# Clock.net
KiCad netlist of a schematic drawn in Altium Designer
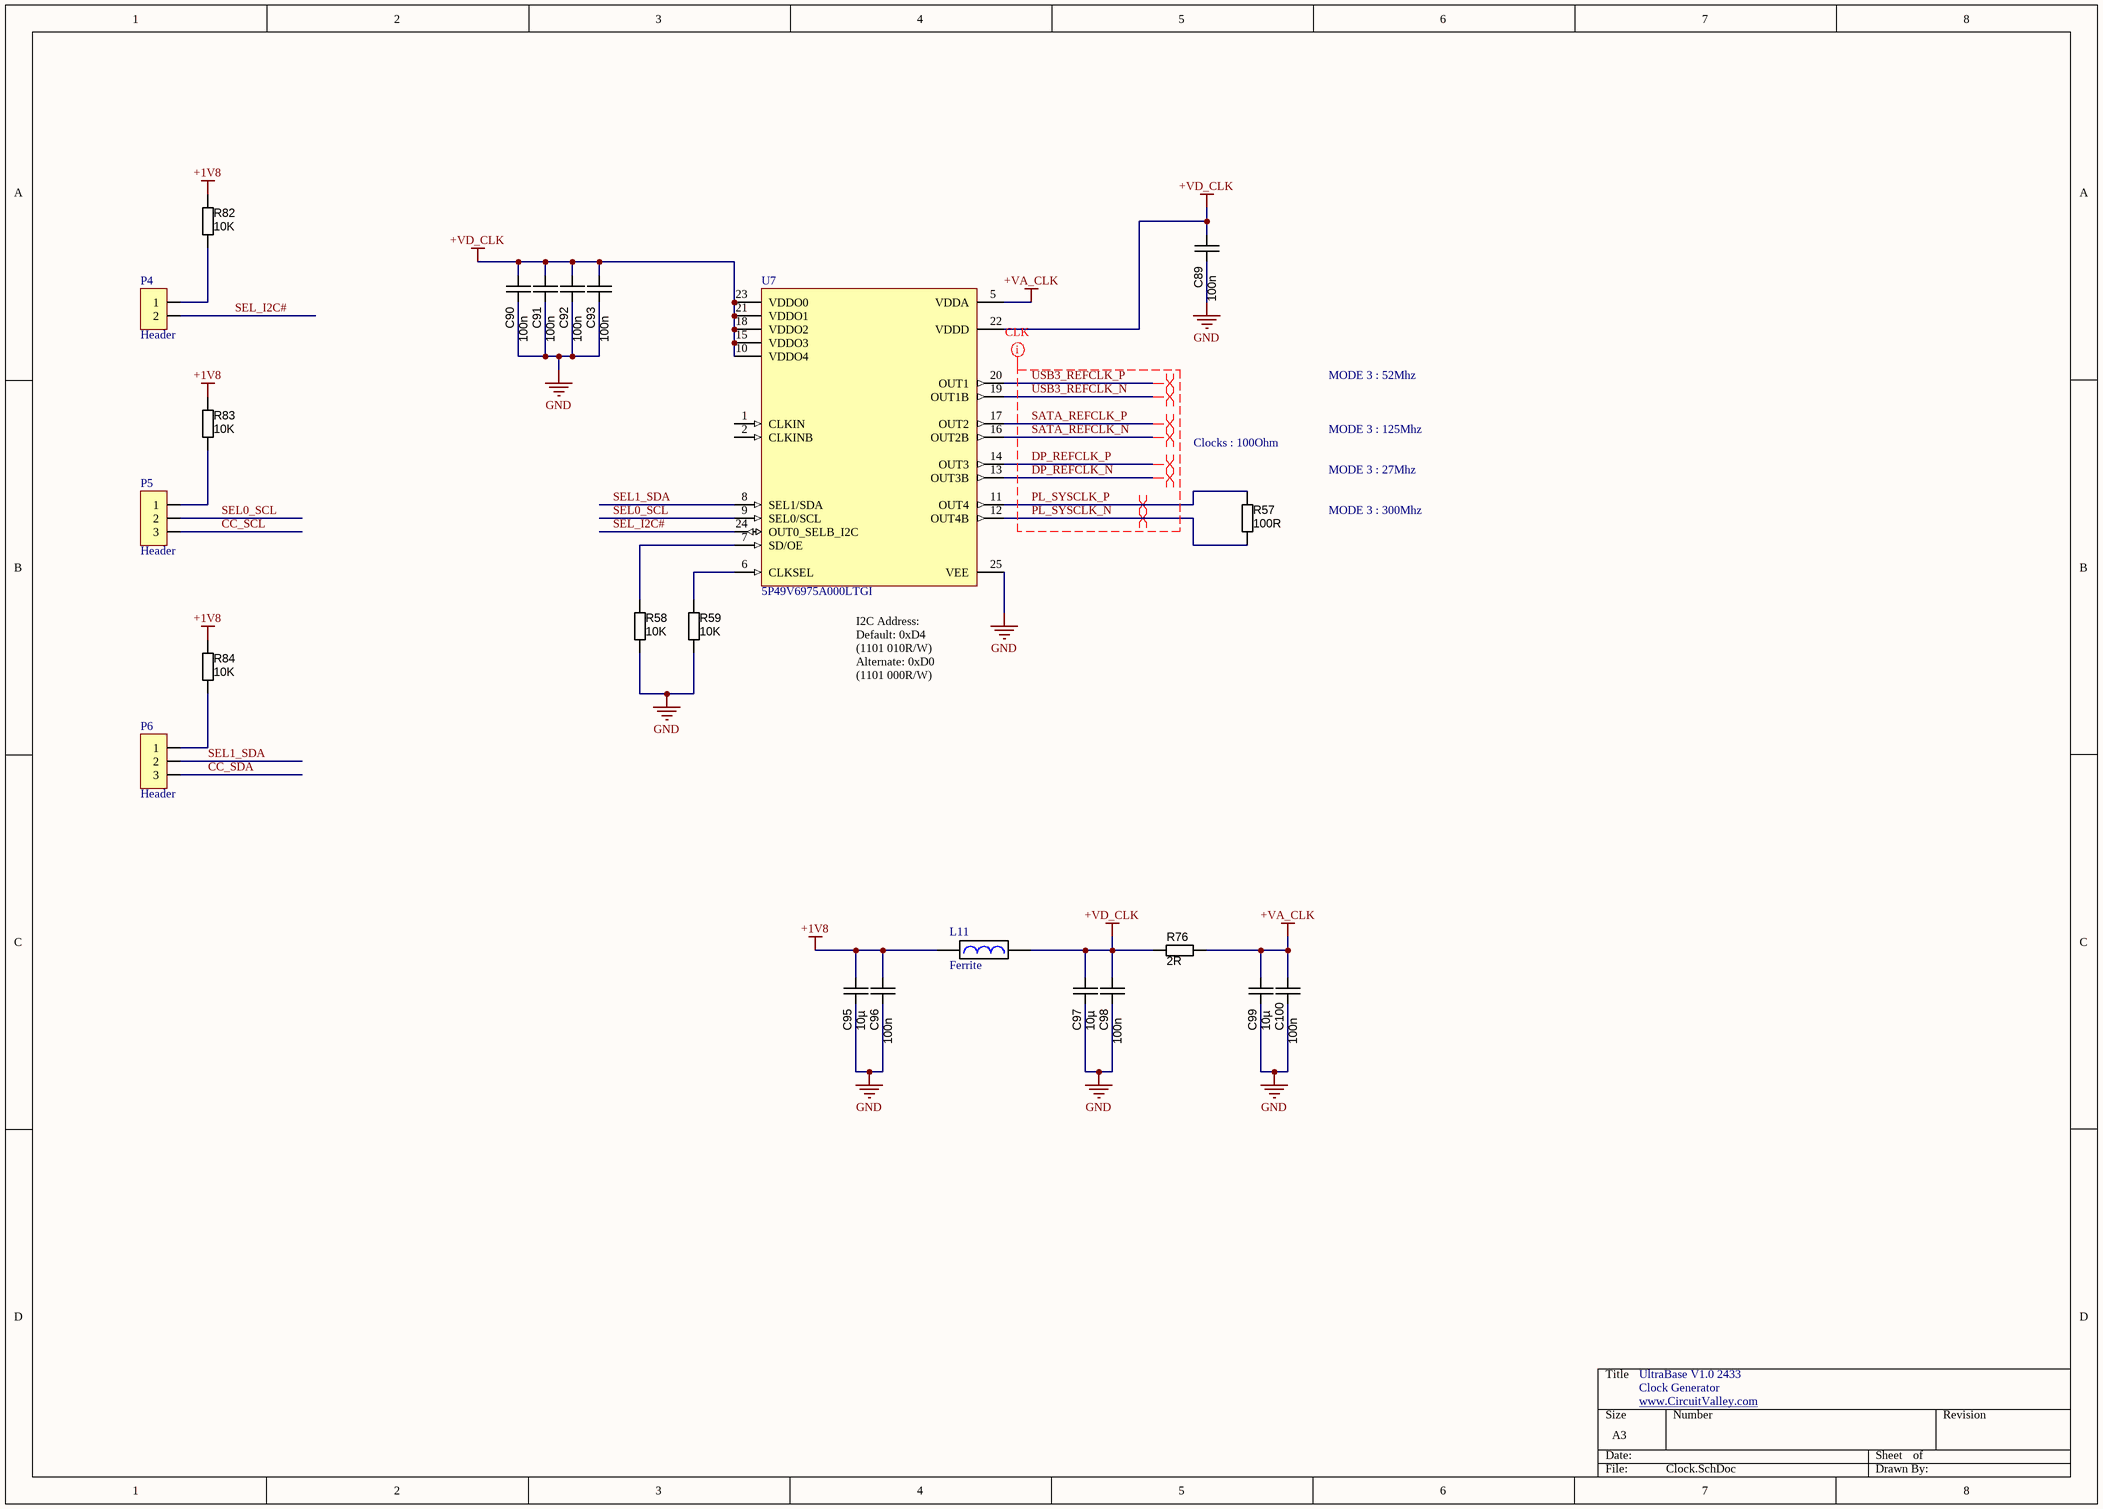
[diagram p0: Clock.SchDoc]

(export (version "E")
  (design (tool "Eeschema 10.0.6"))
  (components
    (comp (ref "C89")
      (value "100n")
      (footprint "CAPC1608N")
      (description "Capacitor SMD Cer 120pF 10% 50V C0G 0603")
      (fields (field (name "TOLERANCE") "±10%"))
      (libsource (lib "PBL - Capacitors") (part "CAPC_120p_0603_C0G_50V"))
    )
    (comp (ref "C90")
      (value "100n")
      (footprint "CAPC1608N")
      (description "Capacitor SMD Cer 120pF 10% 50V C0G 0603")
      (fields (field (name "TOLERANCE") "±10%"))
      (libsource (lib "PBL - Capacitors") (part "CAPC_120p_0603_C0G_50V"))
    )
    (comp (ref "C91")
      (value "100n")
      (footprint "CAPC1608N")
      (description "Capacitor SMD Cer 120pF 10% 50V C0G 0603")
      (fields (field (name "TOLERANCE") "±10%"))
      (libsource (lib "PBL - Capacitors") (part "CAPC_120p_0603_C0G_50V"))
    )
    (comp (ref "C92")
      (value "100n")
      (footprint "CAPC1608N")
      (description "Capacitor SMD Cer 120pF 10% 50V C0G 0603")
      (fields (field (name "TOLERANCE") "±10%"))
      (libsource (lib "PBL - Capacitors") (part "CAPC_120p_0603_C0G_50V"))
    )
    (comp (ref "C93")
      (value "100n")
      (footprint "CAPC1608N")
      (description "Capacitor SMD Cer 120pF 10% 50V C0G 0603")
      (fields (field (name "TOLERANCE") "±10%"))
      (libsource (lib "PBL - Capacitors") (part "CAPC_120p_0603_C0G_50V"))
    )
    (comp (ref "C95")
      (value "10µ")
      (footprint "CAPC3225N")
      (description "Capacitor SMD Cer 10uF 20% 16V X5R 1210")
      (fields (field (name "TOLERANCE") "±20%"))
      (libsource (lib "PBL - Capacitors") (part "CAPC_10u_1210_50V"))
    )
    (comp (ref "C96")
      (value "100n")
      (footprint "CAPC1608N")
      (description "Capacitor SMD Cer 120pF 10% 50V C0G 0603")
      (fields (field (name "TOLERANCE") "±10%"))
      (libsource (lib "PBL - Capacitors") (part "CAPC_120p_0603_C0G_50V"))
    )
    (comp (ref "C97")
      (value "10µ")
      (footprint "CAPC3225N")
      (description "Capacitor SMD Cer 10uF 20% 16V X5R 1210")
      (fields (field (name "TOLERANCE") "±20%"))
      (libsource (lib "PBL - Capacitors") (part "CAPC_10u_1210_50V"))
    )
    (comp (ref "C98")
      (value "100n")
      (footprint "CAPC1608N")
      (description "Capacitor SMD Cer 120pF 10% 50V C0G 0603")
      (fields (field (name "TOLERANCE") "±10%"))
      (libsource (lib "PBL - Capacitors") (part "CAPC_120p_0603_C0G_50V"))
    )
    (comp (ref "C99")
      (value "10µ")
      (footprint "CAPC3225N")
      (description "Capacitor SMD Cer 10uF 20% 16V X5R 1210")
      (fields (field (name "TOLERANCE") "±20%"))
      (libsource (lib "PBL - Capacitors") (part "CAPC_10u_1210_50V"))
    )
    (comp (ref "C100")
      (value "100n")
      (footprint "CAPC1608N")
      (description "Capacitor SMD Cer 120pF 10% 50V C0G 0603")
      (fields (field (name "TOLERANCE") "±10%"))
      (libsource (lib "PBL - Capacitors") (part "CAPC_120p_0603_C0G_50V"))
    )
    (comp (ref "L11")
      (value "Ferrite")
      (footprint "FBC2012N")
      (description "Ferrite Bead")
      (libsource (lib "cvlib") (part "Ferrite Bead"))
    )
    (comp (ref "P4")
      (value "Header")
      (footprint "Header2x")
      (description "2 Pin Header")
      (libsource (lib "cvlib") (part "Header_2Pin"))
    )
    (comp (ref "P5")
      (value "Header")
      (footprint "Header3x")
      (description "3 Pin Header")
      (libsource (lib "cvlib") (part "Header_3Pin"))
    )
    (comp (ref "P6")
      (value "Header")
      (footprint "Header3x")
      (description "3 Pin Header")
      (libsource (lib "cvlib") (part "Header_3Pin"))
    )
    (comp (ref "R57")
      (value "100R")
      (footprint "RESC1608N")
      (description "Resistor, SMD chip")
      (fields (field (name "TOLERANCE") "±5%") (field (name "Comment") "RES_NL_0603"))
      (libsource (lib "") (part "RES_NL_0603_2"))
    )
    (comp (ref "R58")
      (value "10K")
      (footprint "RESC1608N")
      (description "Resistor, SMD chip")
      (fields (field (name "TOLERANCE") "±5%") (field (name "Comment") "RES_NL_0603"))
      (libsource (lib "") (part "RES_NL_0603_1"))
    )
    (comp (ref "R59")
      (value "10K")
      (footprint "RESC1608N")
      (description "Resistor, SMD chip")
      (fields (field (name "TOLERANCE") "±5%") (field (name "Comment") "RES_NL_0603"))
      (libsource (lib "") (part "RES_NL_0603_1"))
    )
    (comp (ref "R76")
      (value "2R")
      (footprint "RESC1608N")
      (description "Resistor, SMD chip")
      (fields (field (name "TOLERANCE") "±5%") (field (name "Comment") "RES_NL_0603"))
      (libsource (lib "PBL - Resistors") (part "RES_NL_0603"))
    )
    (comp (ref "R82")
      (value "10K")
      (footprint "RESC1608N")
      (description "Resistor, SMD chip")
      (fields (field (name "TOLERANCE") "±5%") (field (name "Comment") "RES_NL_0603"))
      (libsource (lib "") (part "RES_NL_0603_1"))
    )
    (comp (ref "R83")
      (value "10K")
      (footprint "RESC1608N")
      (description "Resistor, SMD chip")
      (fields (field (name "TOLERANCE") "±5%") (field (name "Comment") "RES_NL_0603"))
      (libsource (lib "") (part "RES_NL_0603_1"))
    )
    (comp (ref "R84")
      (value "10K")
      (footprint "RESC1608N")
      (description "Resistor, SMD chip")
      (fields (field (name "TOLERANCE") "±5%") (field (name "Comment") "RES_NL_0603"))
      (libsource (lib "") (part "RES_NL_0603_1"))
    )
    (comp (ref "U7")
      (value "5P49V6975A000LTGI")
      (footprint "LGA24")
      (description "Programmable Clock Generators")
      (libsource (lib "cvlib") (part "5P49V6975"))
    )
  )
  (nets
    (net (code "1") (name "+1V8") (class "Default")
      (node (ref "C95") (pin "1") (pintype "passive"))
      (node (ref "C96") (pin "1") (pintype "passive"))
      (node (ref "L11") (pin "1") (pinfunction "1_1") (pintype "passive"))
      (node (ref "R82") (pin "2") (pinfunction "2_2") (pintype "passive"))
      (node (ref "R83") (pin "2") (pinfunction "2_2") (pintype "passive"))
      (node (ref "R84") (pin "2") (pinfunction "2_2") (pintype "passive"))
    )
    (net (code "2") (name "+VA_CLK") (class "Default")
      (node (ref "C100") (pin "1") (pintype "passive"))
      (node (ref "C99") (pin "1") (pintype "passive"))
      (node (ref "R76") (pin "2") (pinfunction "2_2") (pintype "passive"))
      (node (ref "U7") (pin "5") (pinfunction "VDDA_5") (pintype "power_in"))
    )
    (net (code "3") (name "+VD_CLK") (class "Default")
      (node (ref "C89") (pin "1") (pintype "passive"))
      (node (ref "C90") (pin "1") (pintype "passive"))
      (node (ref "C91") (pin "1") (pintype "passive"))
      (node (ref "C92") (pin "1") (pintype "passive"))
      (node (ref "C93") (pin "1") (pintype "passive"))
      (node (ref "C97") (pin "1") (pintype "passive"))
      (node (ref "C98") (pin "1") (pintype "passive"))
      (node (ref "L11") (pin "2") (pinfunction "2_2") (pintype "passive"))
      (node (ref "R76") (pin "1") (pinfunction "1_1") (pintype "passive"))
      (node (ref "U7") (pin "10") (pinfunction "VDDO4_10") (pintype "power_in"))
      (node (ref "U7") (pin "15") (pinfunction "VDDO3_15") (pintype "power_in"))
      (node (ref "U7") (pin "18") (pinfunction "VDDO2_18") (pintype "power_in"))
      (node (ref "U7") (pin "21") (pinfunction "VDDO1_21") (pintype "power_in"))
      (node (ref "U7") (pin "22") (pinfunction "VDDD_22") (pintype "power_in"))
      (node (ref "U7") (pin "23") (pinfunction "VDDO0_23") (pintype "power_in"))
    )
    (net (code "4") (name "/CC_SCL") (class "Default")
      (node (ref "P5") (pin "3") (pinfunction "3_3") (pintype "passive"))
    )
    (net (code "5") (name "/CC_SDA") (class "Default")
      (node (ref "P6") (pin "3") (pinfunction "3_3") (pintype "passive"))
    )
    (net (code "6") (name "/DP_REFCLK_N") (class "Default")
      (node (ref "U7") (pin "13") (pinfunction "OUT3B_13") (pintype "output"))
    )
    (net (code "7") (name "/DP_REFCLK_P") (class "Default")
      (node (ref "U7") (pin "14") (pinfunction "OUT3_14") (pintype "output"))
    )
    (net (code "8") (name "/PL_SYSCLK_N") (class "Default")
      (node (ref "R57") (pin "2") (pinfunction "2_2") (pintype "passive"))
      (node (ref "U7") (pin "12") (pinfunction "OUT4B_12") (pintype "output"))
    )
    (net (code "9") (name "/PL_SYSCLK_P") (class "Default")
      (node (ref "R57") (pin "1") (pinfunction "1_1") (pintype "passive"))
      (node (ref "U7") (pin "11") (pinfunction "OUT4_11") (pintype "output"))
    )
    (net (code "10") (name "/SATA_REFCLK_N") (class "Default")
      (node (ref "U7") (pin "16") (pinfunction "OUT2B_16") (pintype "output"))
    )
    (net (code "11") (name "/SATA_REFCLK_P") (class "Default")
      (node (ref "U7") (pin "17") (pinfunction "OUT2_17") (pintype "output"))
    )
    (net (code "12") (name "/SEL0_SCL") (class "Default")
      (node (ref "P5") (pin "2") (pinfunction "2_2") (pintype "passive"))
      (node (ref "U7") (pin "9") (pinfunction "SEL0/SCL_9") (pintype "input"))
    )
    (net (code "13") (name "/SEL1_SDA") (class "Default")
      (node (ref "P6") (pin "2") (pinfunction "2_2") (pintype "passive"))
      (node (ref "U7") (pin "8") (pinfunction "SEL1/SDA_8") (pintype "input"))
    )
    (net (code "14") (name "/SEL_I2C#") (class "Default")
      (node (ref "P4") (pin "2") (pinfunction "2_2") (pintype "passive"))
      (node (ref "U7") (pin "24") (pinfunction "OUT0_SELB_I2C_24") (pintype "bidirectional"))
    )
    (net (code "15") (name "/USB3_REFCLK_N") (class "Default")
      (node (ref "U7") (pin "19") (pinfunction "OUT1B_19") (pintype "output"))
    )
    (net (code "16") (name "/USB3_REFCLK_P") (class "Default")
      (node (ref "U7") (pin "20") (pinfunction "OUT1_20") (pintype "output"))
    )
    (net (code "17") (name "GND") (class "Default")
      (node (ref "C100") (pin "2") (pintype "passive"))
      (node (ref "C89") (pin "2") (pintype "passive"))
      (node (ref "C90") (pin "2") (pintype "passive"))
      (node (ref "C91") (pin "2") (pintype "passive"))
      (node (ref "C92") (pin "2") (pintype "passive"))
      (node (ref "C93") (pin "2") (pintype "passive"))
      (node (ref "C95") (pin "2") (pintype "passive"))
      (node (ref "C96") (pin "2") (pintype "passive"))
      (node (ref "C97") (pin "2") (pintype "passive"))
      (node (ref "C98") (pin "2") (pintype "passive"))
      (node (ref "C99") (pin "2") (pintype "passive"))
      (node (ref "R58") (pin "1") (pinfunction "1_1") (pintype "passive"))
      (node (ref "R59") (pin "1") (pinfunction "1_1") (pintype "passive"))
      (node (ref "U7") (pin "25") (pinfunction "VEE_25") (pintype "passive"))
    )
    (net (code "18") (name "Net-(P4-Pad1)") (class "Default")
      (node (ref "P4") (pin "1") (pinfunction "1_1") (pintype "passive"))
      (node (ref "R82") (pin "1") (pinfunction "1_1") (pintype "passive"))
    )
    (net (code "19") (name "Net-(P5-Pad1)") (class "Default")
      (node (ref "P5") (pin "1") (pinfunction "1_1") (pintype "passive"))
      (node (ref "R83") (pin "1") (pinfunction "1_1") (pintype "passive"))
    )
    (net (code "20") (name "Net-(P6-Pad1)") (class "Default")
      (node (ref "P6") (pin "1") (pinfunction "1_1") (pintype "passive"))
      (node (ref "R84") (pin "1") (pinfunction "1_1") (pintype "passive"))
    )
    (net (code "21") (name "Net-(U7-CLKSEL)") (class "Default")
      (node (ref "R59") (pin "2") (pinfunction "2_2") (pintype "passive"))
      (node (ref "U7") (pin "6") (pinfunction "CLKSEL_6") (pintype "input"))
    )
    (net (code "22") (name "Net-(U7-SD{slash}OE)") (class "Default")
      (node (ref "R58") (pin "2") (pinfunction "2_2") (pintype "passive"))
      (node (ref "U7") (pin "7") (pinfunction "SD/OE_7") (pintype "input"))
    )
    (net (code "23") (name "unconnected-(U7-CLKIN-Pad1)") (class "Default")
      (node (ref "U7") (pin "1") (pinfunction "CLKIN_1") (pintype "input"))
    )
    (net (code "24") (name "unconnected-(U7-CLKINB-Pad2)") (class "Default")
      (node (ref "U7") (pin "2") (pinfunction "CLKINB_2") (pintype "input"))
    )
  )
)
